# Main.net
KiCad netlist of a schematic drawn in Altium Designer
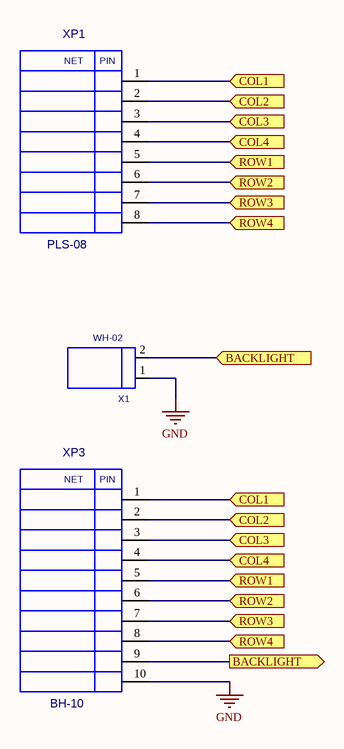
[diagram p0: Main.SchDoc]

(export (version "E")
  (design (tool "Eeschema 10.0.6"))
  (components
    (comp (ref "X1") (value "WH-02") (footprint "WH-02") (libsource (lib "gprs_modem_2") (part "WH-02")))
    (comp (ref "XP1") (value "PLS-08") (footprint "PLS-08") (libsource (lib "gprs_modem_2") (part "PLS-08")))
    (comp (ref "XP3") (value "BH-10") (footprint "BH-10") (libsource (lib "gprs_modem_2") (part "BH-10")))
  )
  (nets
    (net (code "1") (name "/BACKLIGHT") (class "Default")
      (node (ref "X1") (pin "2") (pinfunction "2_2") (pintype "passive"))
      (node (ref "XP3") (pin "9") (pinfunction "9_9") (pintype "passive"))
    )
    (net (code "2") (name "/COL1") (class "Default")
      (node (ref "XP1") (pin "1") (pinfunction "1_1") (pintype "passive"))
      (node (ref "XP3") (pin "1") (pinfunction "1_1") (pintype "passive"))
    )
    (net (code "3") (name "/COL2") (class "Default")
      (node (ref "XP1") (pin "2") (pinfunction "2_2") (pintype "passive"))
      (node (ref "XP3") (pin "2") (pinfunction "2_2") (pintype "passive"))
    )
    (net (code "4") (name "/COL3") (class "Default")
      (node (ref "XP1") (pin "3") (pinfunction "3_3") (pintype "passive"))
      (node (ref "XP3") (pin "3") (pinfunction "3_3") (pintype "passive"))
    )
    (net (code "5") (name "/COL4") (class "Default")
      (node (ref "XP1") (pin "4") (pinfunction "4_4") (pintype "passive"))
      (node (ref "XP3") (pin "4") (pinfunction "4_4") (pintype "passive"))
    )
    (net (code "6") (name "/ROW1") (class "Default")
      (node (ref "XP1") (pin "5") (pinfunction "5_5") (pintype "passive"))
      (node (ref "XP3") (pin "5") (pinfunction "5_5") (pintype "passive"))
    )
    (net (code "7") (name "/ROW2") (class "Default")
      (node (ref "XP1") (pin "6") (pinfunction "6_6") (pintype "passive"))
      (node (ref "XP3") (pin "6") (pinfunction "6_6") (pintype "passive"))
    )
    (net (code "8") (name "/ROW3") (class "Default")
      (node (ref "XP1") (pin "7") (pinfunction "7_7") (pintype "passive"))
      (node (ref "XP3") (pin "7") (pinfunction "7_7") (pintype "passive"))
    )
    (net (code "9") (name "/ROW4") (class "Default")
      (node (ref "XP1") (pin "8") (pinfunction "8_8") (pintype "passive"))
      (node (ref "XP3") (pin "8") (pinfunction "8_8") (pintype "passive"))
    )
    (net (code "10") (name "GND") (class "Default")
      (node (ref "X1") (pin "1") (pinfunction "1_1") (pintype "passive"))
      (node (ref "XP3") (pin "10") (pinfunction "10_10") (pintype "passive"))
    )
  )
)
